# calibration-hw.net
KiCad netlist of a schematic drawn in Altium Designer
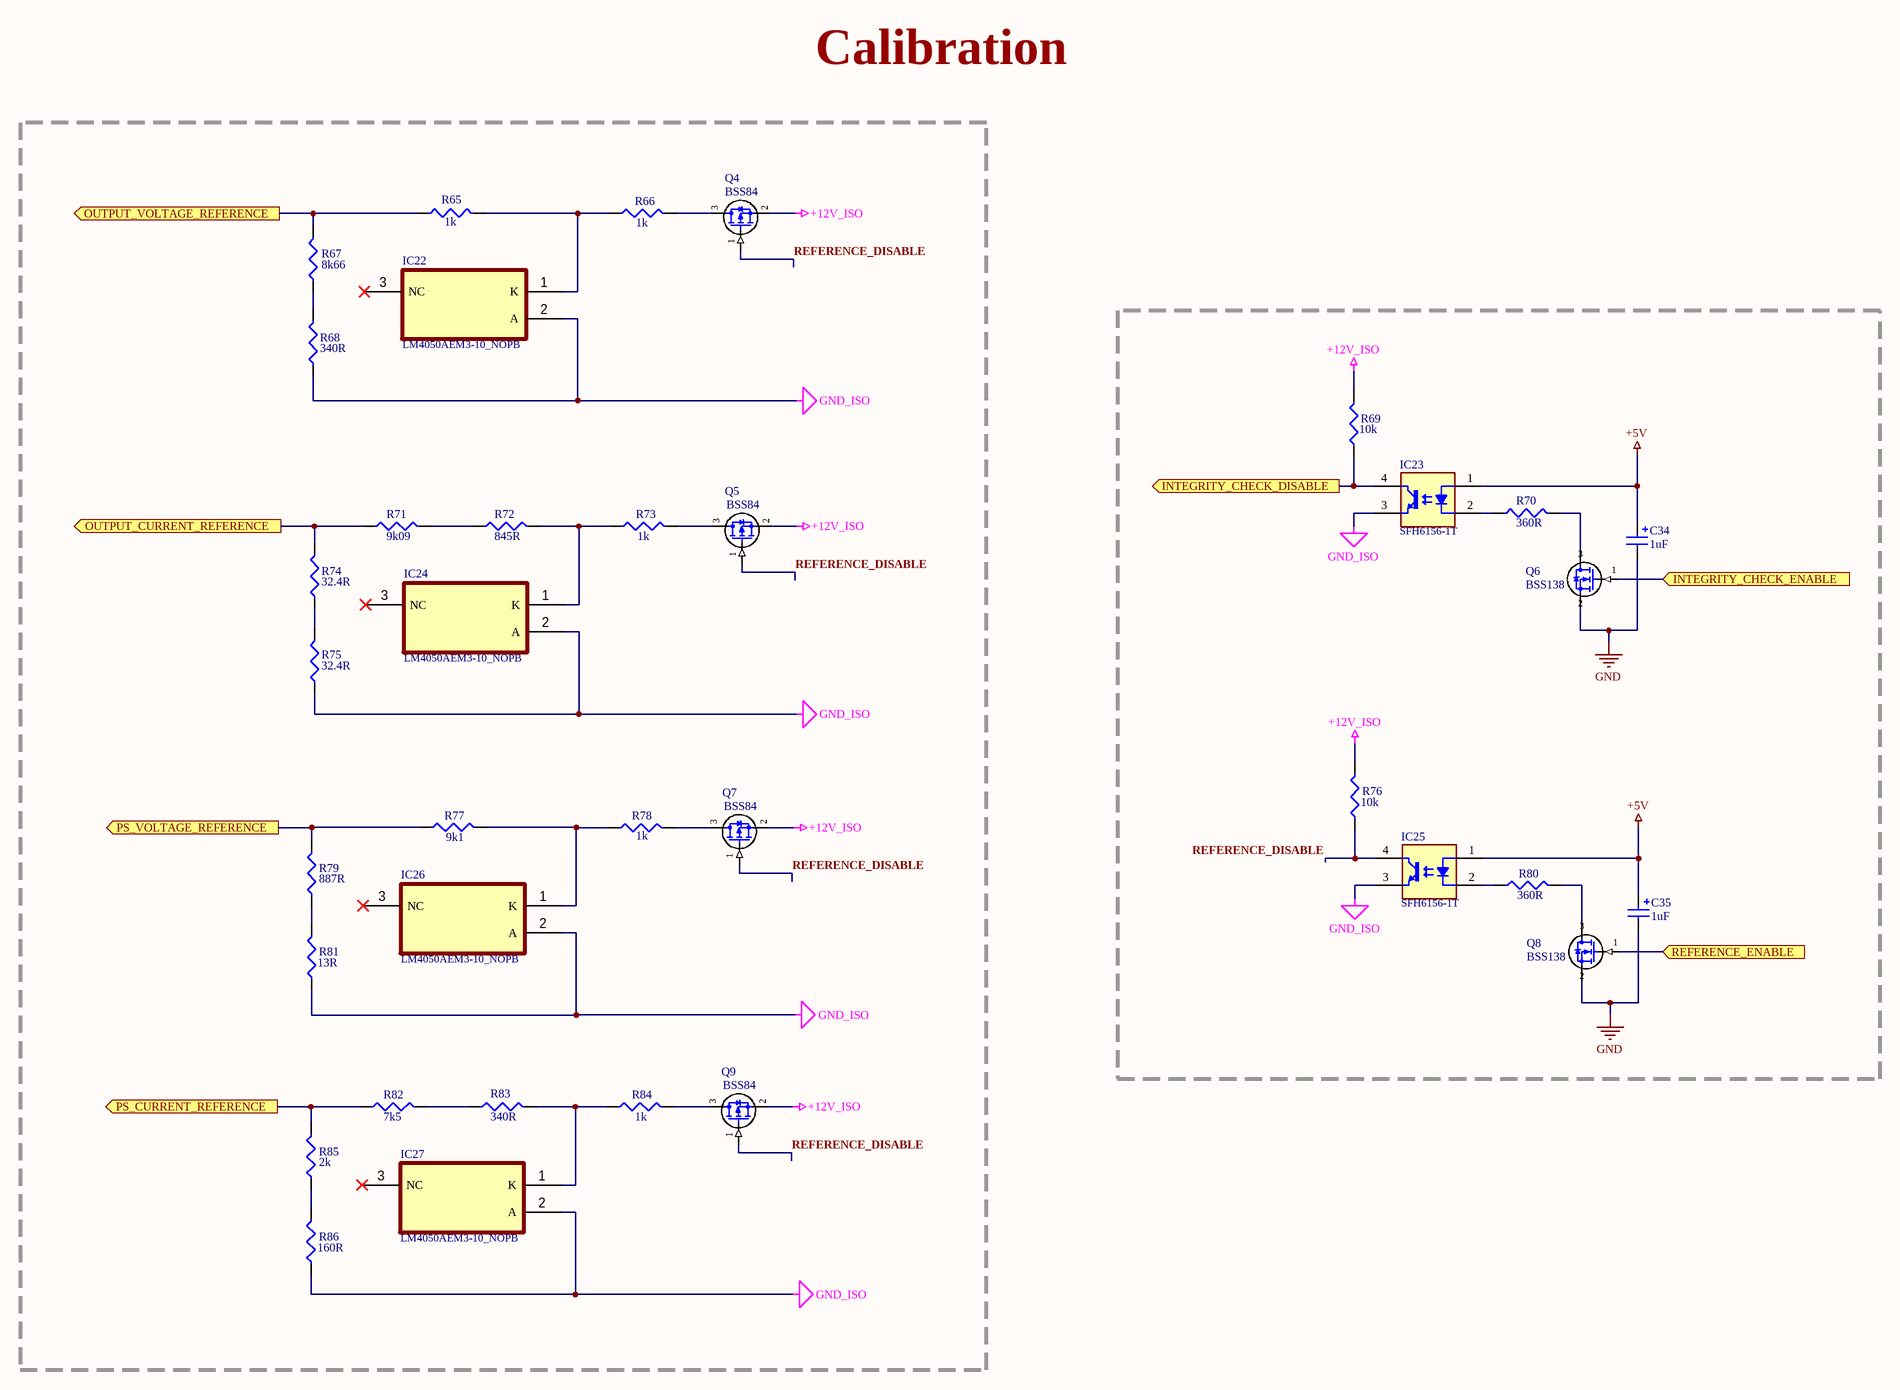
[diagram p0: calibration-hw.SchDoc]

(export (version "E")
  (design (tool "Eeschema 10.0.6"))
  (components
    (comp (ref "C34")
      (value "1uF")
      (footprint "C1206")
      (libsource (lib "acopians-powerspy-monitoring-hw-library-schematic") (part "Capacitor 1uF"))
    )
    (comp (ref "C35")
      (value "1uF")
      (footprint "C1206")
      (libsource (lib "acopians-powerspy-monitoring-hw-library-schematic") (part "Capacitor 1uF"))
    )
    (comp (ref "IC22")
      (value "LM4050AEM3-10_NOPB")
      (footprint "SOT_23_3")
      (description "Precision Micropower Shunt Voltage Reference")
      (libsource (lib "acopians-powerspy-monitoring-hw-library-schematic") (part "LM4050AEM3-10_NOPB"))
    )
    (comp (ref "IC23")
      (value "SFH6156-1T")
      (footprint "SMD-4")
      (description "Optocoupler 1 Channel, Phototransistor Output, SMD-4")
      (libsource (lib "acopians-powerspy-monitoring-hw-library-schematic") (part "SFH6156-1T"))
    )
    (comp (ref "IC24")
      (value "LM4050AEM3-10_NOPB")
      (footprint "SOT_23_3")
      (description "Precision Micropower Shunt Voltage Reference")
      (libsource (lib "acopians-powerspy-monitoring-hw-library-schematic") (part "LM4050AEM3-10_NOPB"))
    )
    (comp (ref "IC25")
      (value "SFH6156-1T")
      (footprint "SMD-4")
      (description "Optocoupler 1 Channel, Phototransistor Output, SMD-4")
      (libsource (lib "acopians-powerspy-monitoring-hw-library-schematic") (part "SFH6156-1T"))
    )
    (comp (ref "IC26")
      (value "LM4050AEM3-10_NOPB")
      (footprint "SOT_23_3")
      (description "Precision Micropower Shunt Voltage Reference")
      (libsource (lib "acopians-powerspy-monitoring-hw-library-schematic") (part "LM4050AEM3-10_NOPB"))
    )
    (comp (ref "IC27")
      (value "LM4050AEM3-10_NOPB")
      (footprint "SOT_23_3")
      (description "Precision Micropower Shunt Voltage Reference")
      (libsource (lib "acopians-powerspy-monitoring-hw-library-schematic") (part "LM4050AEM3-10_NOPB"))
    )
    (comp (ref "Q4")
      (value "BSS84")
      (footprint "SOT_23_3")
      (description "MOSFET P-Channel")
      (libsource (lib "acopians-powerspy-monitoring-hw-library-schematic") (part "BSS84"))
    )
    (comp (ref "Q5")
      (value "BSS84")
      (footprint "SOT_23_3")
      (description "MOSFET P-Channel")
      (libsource (lib "acopians-powerspy-monitoring-hw-library-schematic") (part "BSS84"))
    )
    (comp (ref "Q6")
      (value "BSS138")
      (footprint "SOT_23_3")
      (description "MOSFET N-Channel")
      (libsource (lib "acopians-powerspy-monitoring-hw-library-schematic") (part "BSS138"))
    )
    (comp (ref "Q7")
      (value "BSS84")
      (footprint "SOT_23_3")
      (description "MOSFET P-Channel")
      (libsource (lib "acopians-powerspy-monitoring-hw-library-schematic") (part "BSS84"))
    )
    (comp (ref "Q8")
      (value "BSS138")
      (footprint "SOT_23_3")
      (description "MOSFET N-Channel")
      (libsource (lib "acopians-powerspy-monitoring-hw-library-schematic") (part "BSS138"))
    )
    (comp (ref "Q9")
      (value "BSS84")
      (footprint "SOT_23_3")
      (description "MOSFET P-Channel")
      (libsource (lib "acopians-powerspy-monitoring-hw-library-schematic") (part "BSS84"))
    )
    (comp (ref "R65")
      (value "1k")
      (footprint "Resistor 0805")
      (libsource (lib "acopians-powerspy-monitoring-hw-library-schematic") (part "Resistor 1k"))
    )
    (comp (ref "R66")
      (value "1k")
      (footprint "Resistor 0805")
      (libsource (lib "acopians-powerspy-monitoring-hw-library-schematic") (part "Resistor 1k"))
    )
    (comp (ref "R67")
      (value "8k66")
      (footprint "Resistor 0805")
      (libsource (lib "acopians-powerspy-monitoring-hw-library-schematic") (part "Resistor 8k66"))
    )
    (comp (ref "R68")
      (value "340R")
      (footprint "Resistor 0805")
      (libsource (lib "acopians-powerspy-monitoring-hw-library-schematic") (part "Resistor 340R"))
    )
    (comp (ref "R69")
      (value "10k")
      (footprint "Resistor 0805")
      (libsource (lib "acopians-powerspy-monitoring-hw-library-schematic") (part "Resistor 10k"))
    )
    (comp (ref "R70")
      (value "360R")
      (footprint "Resistor 0805")
      (libsource (lib "acopians-powerspy-monitoring-hw-library-schematic") (part "Resistor 360R"))
    )
    (comp (ref "R71")
      (value "9k09")
      (footprint "Resistor 0805")
      (libsource (lib "acopians-powerspy-monitoring-hw-library-schematic") (part "Resistor 9k09"))
    )
    (comp (ref "R72")
      (value "845R")
      (footprint "Resistor 0805")
      (libsource (lib "acopians-powerspy-monitoring-hw-library-schematic") (part "Resistor 845R"))
    )
    (comp (ref "R73")
      (value "1k")
      (footprint "Resistor 0805")
      (libsource (lib "acopians-powerspy-monitoring-hw-library-schematic") (part "Resistor 1k"))
    )
    (comp (ref "R74")
      (value "32.4R")
      (footprint "Resistor 0805")
      (libsource (lib "acopians-powerspy-monitoring-hw-library-schematic") (part "Resistor 32.4R"))
    )
    (comp (ref "R75")
      (value "32.4R")
      (footprint "Resistor 0805")
      (libsource (lib "acopians-powerspy-monitoring-hw-library-schematic") (part "Resistor 32.4R"))
    )
    (comp (ref "R76")
      (value "10k")
      (footprint "Resistor 0805")
      (libsource (lib "acopians-powerspy-monitoring-hw-library-schematic") (part "Resistor 10k"))
    )
    (comp (ref "R77")
      (value "9k1")
      (footprint "Resistor 0805")
      (libsource (lib "acopians-powerspy-monitoring-hw-library-schematic") (part "Resistor 9k1"))
    )
    (comp (ref "R78")
      (value "1k")
      (footprint "Resistor 0805")
      (libsource (lib "acopians-powerspy-monitoring-hw-library-schematic") (part "Resistor 1k"))
    )
    (comp (ref "R79")
      (value "887R")
      (footprint "Resistor 0805")
      (libsource (lib "acopians-powerspy-monitoring-hw-library-schematic") (part "Resistor 887R"))
    )
    (comp (ref "R80")
      (value "360R")
      (footprint "Resistor 0805")
      (libsource (lib "acopians-powerspy-monitoring-hw-library-schematic") (part "Resistor 360R"))
    )
    (comp (ref "R81")
      (value "13R")
      (footprint "Resistor 0805")
      (libsource (lib "acopians-powerspy-monitoring-hw-library-schematic") (part "Resistor 13R"))
    )
    (comp (ref "R82")
      (value "7k5")
      (footprint "Resistor 0805")
      (libsource (lib "acopians-powerspy-monitoring-hw-library-schematic") (part "Resistor 7k5"))
    )
    (comp (ref "R83")
      (value "340R")
      (footprint "Resistor 0805")
      (libsource (lib "acopians-powerspy-monitoring-hw-library-schematic") (part "Resistor 340R"))
    )
    (comp (ref "R84")
      (value "1k")
      (footprint "Resistor 0805")
      (libsource (lib "acopians-powerspy-monitoring-hw-library-schematic") (part "Resistor 1k"))
    )
    (comp (ref "R85")
      (value "2k")
      (footprint "Resistor 0805")
      (libsource (lib "acopians-powerspy-monitoring-hw-library-schematic") (part "Resistor 2k"))
    )
    (comp (ref "R86")
      (value "160R")
      (footprint "Resistor 0805")
      (libsource (lib "acopians-powerspy-monitoring-hw-library-schematic") (part "Resistor 160R"))
    )
  )
  (nets
    (net (code "1") (name "+5V") (class "Default")
      (node (ref "C34") (pin "1") (pinfunction "1_1") (pintype "passive"))
      (node (ref "C35") (pin "1") (pinfunction "1_1") (pintype "passive"))
      (node (ref "IC23") (pin "1") (pinfunction "A_1") (pintype "passive"))
      (node (ref "IC25") (pin "1") (pinfunction "A_1") (pintype "passive"))
    )
    (net (code "2") (name "+12V_ISO") (class "Default")
      (node (ref "Q4") (pin "2") (pinfunction "S_2") (pintype "passive"))
      (node (ref "Q5") (pin "2") (pinfunction "S_2") (pintype "passive"))
      (node (ref "Q7") (pin "2") (pinfunction "S_2") (pintype "passive"))
      (node (ref "Q9") (pin "2") (pinfunction "S_2") (pintype "passive"))
      (node (ref "R69") (pin "2") (pinfunction "2_2") (pintype "passive"))
      (node (ref "R76") (pin "2") (pinfunction "2_2") (pintype "passive"))
    )
    (net (code "3") (name "/INTEGRITY_CHECK_DISABLE") (class "Default")
      (node (ref "IC23") (pin "4") (pinfunction "C_4") (pintype "open_collector"))
      (node (ref "R69") (pin "1") (pinfunction "1_1") (pintype "passive"))
    )
    (net (code "4") (name "/INTEGRITY_CHECK_ENABLE") (class "Default")
      (node (ref "Q6") (pin "1") (pinfunction "G_1") (pintype "input"))
    )
    (net (code "5") (name "/OUTPUT_CURRENT_REFERENCE") (class "Default")
      (node (ref "R71") (pin "1") (pinfunction "1_1") (pintype "passive"))
      (node (ref "R74") (pin "2") (pinfunction "2_2") (pintype "passive"))
    )
    (net (code "6") (name "/OUTPUT_VOLTAGE_REFERENCE") (class "Default")
      (node (ref "R65") (pin "1") (pinfunction "1_1") (pintype "passive"))
      (node (ref "R67") (pin "2") (pinfunction "2_2") (pintype "passive"))
    )
    (net (code "7") (name "/PS_CURRENT_REFERENCE") (class "Default")
      (node (ref "R82") (pin "1") (pinfunction "1_1") (pintype "passive"))
      (node (ref "R85") (pin "2") (pinfunction "2_2") (pintype "passive"))
    )
    (net (code "8") (name "/PS_VOLTAGE_REFERENCE") (class "Default")
      (node (ref "R77") (pin "1") (pinfunction "1_1") (pintype "passive"))
      (node (ref "R79") (pin "2") (pinfunction "2_2") (pintype "passive"))
    )
    (net (code "9") (name "/REFERENCE_DISABLE") (class "Default")
      (node (ref "IC25") (pin "4") (pinfunction "C_4") (pintype "open_collector"))
      (node (ref "Q4") (pin "1") (pinfunction "G_1") (pintype "input"))
      (node (ref "Q5") (pin "1") (pinfunction "G_1") (pintype "input"))
      (node (ref "Q7") (pin "1") (pinfunction "G_1") (pintype "input"))
      (node (ref "Q9") (pin "1") (pinfunction "G_1") (pintype "input"))
      (node (ref "R76") (pin "1") (pinfunction "1_1") (pintype "passive"))
    )
    (net (code "10") (name "/REFERENCE_ENABLE") (class "Default")
      (node (ref "Q8") (pin "1") (pinfunction "G_1") (pintype "input"))
    )
    (net (code "11") (name "GND") (class "Default")
      (node (ref "C34") (pin "2") (pinfunction "2_2") (pintype "passive"))
      (node (ref "C35") (pin "2") (pinfunction "2_2") (pintype "passive"))
      (node (ref "Q6") (pin "2") (pinfunction "S_2") (pintype "passive"))
      (node (ref "Q8") (pin "2") (pinfunction "S_2") (pintype "passive"))
    )
    (net (code "12") (name "GND_ISO") (class "Default")
      (node (ref "IC22") (pin "2") (pinfunction "A_2") (pintype "passive"))
      (node (ref "IC23") (pin "3") (pinfunction "E_3") (pintype "open_emitter"))
      (node (ref "IC24") (pin "2") (pinfunction "A_2") (pintype "passive"))
      (node (ref "IC25") (pin "3") (pinfunction "E_3") (pintype "open_emitter"))
      (node (ref "IC26") (pin "2") (pinfunction "A_2") (pintype "passive"))
      (node (ref "IC27") (pin "2") (pinfunction "A_2") (pintype "passive"))
      (node (ref "R68") (pin "1") (pinfunction "1_1") (pintype "passive"))
      (node (ref "R75") (pin "1") (pinfunction "1_1") (pintype "passive"))
      (node (ref "R81") (pin "1") (pinfunction "1_1") (pintype "passive"))
      (node (ref "R86") (pin "1") (pinfunction "1_1") (pintype "passive"))
    )
    (net (code "13") (name "Net-(IC22-K)") (class "Default")
      (node (ref "IC22") (pin "1") (pinfunction "K_1") (pintype "passive"))
      (node (ref "R65") (pin "2") (pinfunction "2_2") (pintype "passive"))
      (node (ref "R66") (pin "1") (pinfunction "1_1") (pintype "passive"))
    )
    (net (code "14") (name "Net-(IC23-C-Pad2)") (class "Default")
      (node (ref "IC23") (pin "2") (pinfunction "C_2") (pintype "passive"))
      (node (ref "R70") (pin "1") (pinfunction "1_1") (pintype "passive"))
    )
    (net (code "15") (name "Net-(IC24-K)") (class "Default")
      (node (ref "IC24") (pin "1") (pinfunction "K_1") (pintype "passive"))
      (node (ref "R72") (pin "2") (pinfunction "2_2") (pintype "passive"))
      (node (ref "R73") (pin "1") (pinfunction "1_1") (pintype "passive"))
    )
    (net (code "16") (name "Net-(IC25-C-Pad2)") (class "Default")
      (node (ref "IC25") (pin "2") (pinfunction "C_2") (pintype "passive"))
      (node (ref "R80") (pin "1") (pinfunction "1_1") (pintype "passive"))
    )
    (net (code "17") (name "Net-(IC26-K)") (class "Default")
      (node (ref "IC26") (pin "1") (pinfunction "K_1") (pintype "passive"))
      (node (ref "R77") (pin "2") (pinfunction "2_2") (pintype "passive"))
      (node (ref "R78") (pin "1") (pinfunction "1_1") (pintype "passive"))
    )
    (net (code "18") (name "Net-(IC27-K)") (class "Default")
      (node (ref "IC27") (pin "1") (pinfunction "K_1") (pintype "passive"))
      (node (ref "R83") (pin "2") (pinfunction "2_2") (pintype "passive"))
      (node (ref "R84") (pin "1") (pinfunction "1_1") (pintype "passive"))
    )
    (net (code "19") (name "Net-(Q4-D)") (class "Default")
      (node (ref "Q4") (pin "3") (pinfunction "D_3") (pintype "passive"))
      (node (ref "R66") (pin "2") (pinfunction "2_2") (pintype "passive"))
    )
    (net (code "20") (name "Net-(Q5-D)") (class "Default")
      (node (ref "Q5") (pin "3") (pinfunction "D_3") (pintype "passive"))
      (node (ref "R73") (pin "2") (pinfunction "2_2") (pintype "passive"))
    )
    (net (code "21") (name "Net-(Q6-D)") (class "Default")
      (node (ref "Q6") (pin "3") (pinfunction "D_3") (pintype "passive"))
      (node (ref "R70") (pin "2") (pinfunction "2_2") (pintype "passive"))
    )
    (net (code "22") (name "Net-(Q7-D)") (class "Default")
      (node (ref "Q7") (pin "3") (pinfunction "D_3") (pintype "passive"))
      (node (ref "R78") (pin "2") (pinfunction "2_2") (pintype "passive"))
    )
    (net (code "23") (name "Net-(Q8-D)") (class "Default")
      (node (ref "Q8") (pin "3") (pinfunction "D_3") (pintype "passive"))
      (node (ref "R80") (pin "2") (pinfunction "2_2") (pintype "passive"))
    )
    (net (code "24") (name "Net-(Q9-D)") (class "Default")
      (node (ref "Q9") (pin "3") (pinfunction "D_3") (pintype "passive"))
      (node (ref "R84") (pin "2") (pinfunction "2_2") (pintype "passive"))
    )
    (net (code "25") (name "Net-(R67-Pad1)") (class "Default")
      (node (ref "R67") (pin "1") (pinfunction "1_1") (pintype "passive"))
      (node (ref "R68") (pin "2") (pinfunction "2_2") (pintype "passive"))
    )
    (net (code "26") (name "Net-(R71-Pad2)") (class "Default")
      (node (ref "R71") (pin "2") (pinfunction "2_2") (pintype "passive"))
      (node (ref "R72") (pin "1") (pinfunction "1_1") (pintype "passive"))
    )
    (net (code "27") (name "Net-(R74-Pad1)") (class "Default")
      (node (ref "R74") (pin "1") (pinfunction "1_1") (pintype "passive"))
      (node (ref "R75") (pin "2") (pinfunction "2_2") (pintype "passive"))
    )
    (net (code "28") (name "Net-(R79-Pad1)") (class "Default")
      (node (ref "R79") (pin "1") (pinfunction "1_1") (pintype "passive"))
      (node (ref "R81") (pin "2") (pinfunction "2_2") (pintype "passive"))
    )
    (net (code "29") (name "Net-(R82-Pad2)") (class "Default")
      (node (ref "R82") (pin "2") (pinfunction "2_2") (pintype "passive"))
      (node (ref "R83") (pin "1") (pinfunction "1_1") (pintype "passive"))
    )
    (net (code "30") (name "Net-(R85-Pad1)") (class "Default")
      (node (ref "R85") (pin "1") (pinfunction "1_1") (pintype "passive"))
      (node (ref "R86") (pin "2") (pinfunction "2_2") (pintype "passive"))
    )
    (net (code "31") (name "unconnected-(IC22-NC-Pad3)") (class "Default")
      (node (ref "IC22") (pin "3") (pinfunction "NC_3") (pintype "passive+no_connect"))
    )
    (net (code "32") (name "unconnected-(IC24-NC-Pad3)") (class "Default")
      (node (ref "IC24") (pin "3") (pinfunction "NC_3") (pintype "passive+no_connect"))
    )
    (net (code "33") (name "unconnected-(IC26-NC-Pad3)") (class "Default")
      (node (ref "IC26") (pin "3") (pinfunction "NC_3") (pintype "passive+no_connect"))
    )
    (net (code "34") (name "unconnected-(IC27-NC-Pad3)") (class "Default")
      (node (ref "IC27") (pin "3") (pinfunction "NC_3") (pintype "passive+no_connect"))
    )
  )
)
